# FredT232H_Board.net
KiCad netlist of a schematic drawn in EAGLE
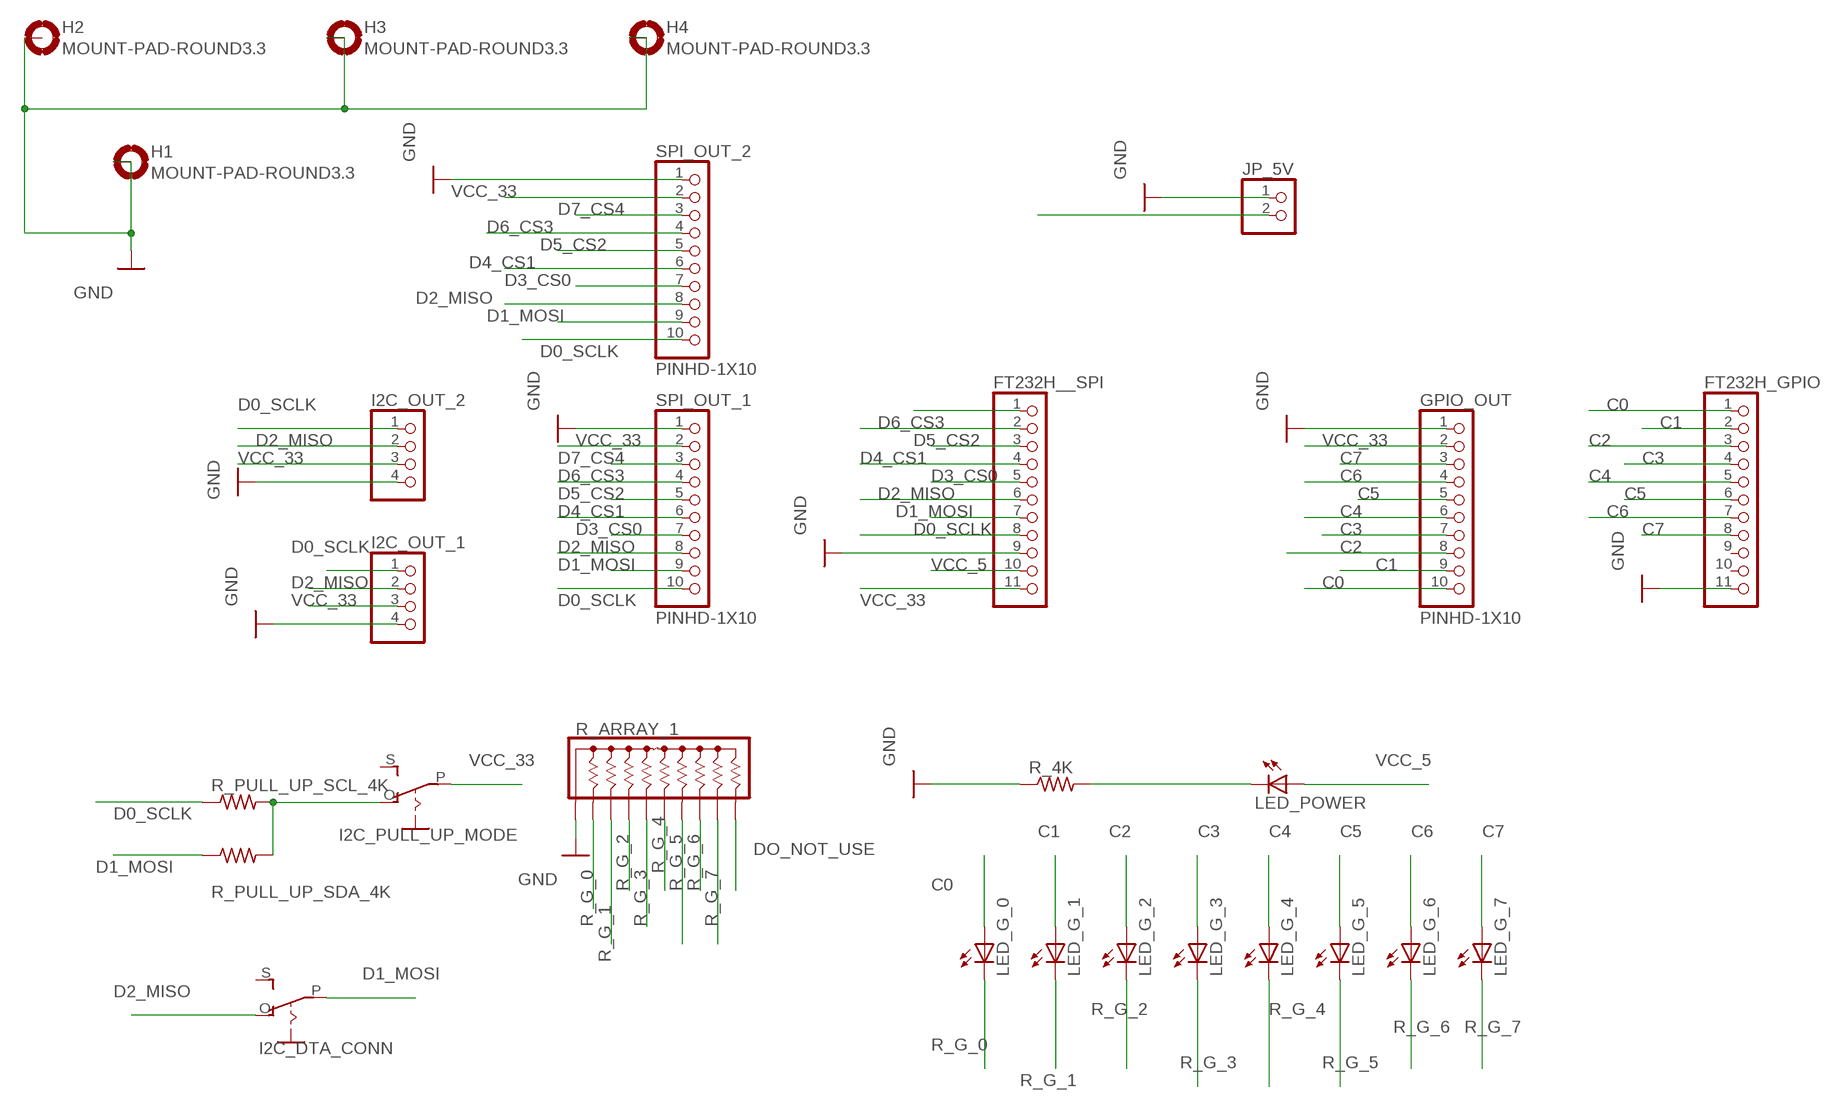
[diagram p0: schematic, sheet 1]

(export (version "E")
  (design (tool "Eeschema 10.0.6"))
  (components
    (comp (ref "FT232H_GPIO")
      (value "PINHD-1X11")
      (footprint "eagle-import:1X11")
      (libsource (lib "eagle-import") (part "PINHD-1X11"))
    )
    (comp (ref "FT232H__SPI")
      (value "PINHD-1X11")
      (footprint "eagle-import:1X11")
      (libsource (lib "eagle-import") (part "PINHD-1X11"))
    )
    (comp (ref "GPIO_OUT")
      (value "PINHD-1X10")
      (footprint "eagle-import:1X10-BIG")
      (libsource (lib "eagle-import") (part "PINHD-1X10"))
    )
    (comp (ref "H1")
      (value "MOUNT-PAD-ROUND3.3")
      (footprint "eagle-import:3,3-PAD")
      (libsource (lib "eagle-import") (part "MOUNT-PAD-ROUND3.3"))
    )
    (comp (ref "H2")
      (value "MOUNT-PAD-ROUND3.3")
      (footprint "eagle-import:3,3-PAD")
      (libsource (lib "eagle-import") (part "MOUNT-PAD-ROUND3.3"))
    )
    (comp (ref "H3")
      (value "MOUNT-PAD-ROUND3.3")
      (footprint "eagle-import:3,3-PAD")
      (libsource (lib "eagle-import") (part "MOUNT-PAD-ROUND3.3"))
    )
    (comp (ref "H4")
      (value "MOUNT-PAD-ROUND3.3")
      (footprint "eagle-import:3,3-PAD")
      (libsource (lib "eagle-import") (part "MOUNT-PAD-ROUND3.3"))
    )
    (comp (ref "I2C_DTA_CONN")
      (value "EG1218S")
      (footprint "eagle-import:EG1218")
      (libsource (lib "eagle-import") (part "EG1218S"))
    )
    (comp (ref "I2C_OUT_1")
      (value "PINHD-1X4")
      (footprint "eagle-import:1X04")
      (libsource (lib "eagle-import") (part "PINHD-1X4"))
    )
    (comp (ref "I2C_OUT_2")
      (value "PINHD-1X4")
      (footprint "eagle-import:1X04")
      (libsource (lib "eagle-import") (part "PINHD-1X4"))
    )
    (comp (ref "I2C_PULL_UP_MODE")
      (value "EG1218S")
      (footprint "eagle-import:EG1218")
      (libsource (lib "eagle-import") (part "EG1218S"))
    )
    (comp (ref "JP_5V")
      (value "PINHD-1X2")
      (footprint "eagle-import:1X02")
      (libsource (lib "eagle-import") (part "PINHD-1X2"))
    )
    (comp (ref "LED_G_0")
      (value "LEDSMT1206")
      (footprint "eagle-import:1206")
      (libsource (lib "eagle-import") (part "LEDSMT1206"))
    )
    (comp (ref "LED_G_1")
      (value "LEDSMT1206")
      (footprint "eagle-import:1206")
      (libsource (lib "eagle-import") (part "LEDSMT1206"))
    )
    (comp (ref "LED_G_2")
      (value "LEDSMT1206")
      (footprint "eagle-import:1206")
      (libsource (lib "eagle-import") (part "LEDSMT1206"))
    )
    (comp (ref "LED_G_3")
      (value "LEDSMT1206")
      (footprint "eagle-import:1206")
      (libsource (lib "eagle-import") (part "LEDSMT1206"))
    )
    (comp (ref "LED_G_4")
      (value "LEDSMT1206")
      (footprint "eagle-import:1206")
      (libsource (lib "eagle-import") (part "LEDSMT1206"))
    )
    (comp (ref "LED_G_5")
      (value "LEDSMT1206")
      (footprint "eagle-import:1206")
      (libsource (lib "eagle-import") (part "LEDSMT1206"))
    )
    (comp (ref "LED_G_6")
      (value "LEDSMT1206")
      (footprint "eagle-import:1206")
      (libsource (lib "eagle-import") (part "LEDSMT1206"))
    )
    (comp (ref "LED_G_7")
      (value "LEDSMT1206")
      (footprint "eagle-import:1206")
      (libsource (lib "eagle-import") (part "LEDSMT1206"))
    )
    (comp (ref "LED_POWER")
      (value "LEDSMT1206")
      (footprint "eagle-import:1206")
      (libsource (lib "eagle-import") (part "LEDSMT1206"))
    )
    (comp (ref "R_4K")
      (value "R-US_R1206")
      (footprint "eagle-import:R1206")
      (libsource (lib "eagle-import") (part "R-US_R1206"))
    )
    (comp (ref "R_ARRAY_1")
      (value "4610X")
      (footprint "eagle-import:SIP10")
      (libsource (lib "eagle-import") (part "4610X"))
    )
    (comp (ref "R_PULL_UP_SCL_4K")
      (value "R-US_R1206")
      (footprint "eagle-import:R1206")
      (libsource (lib "eagle-import") (part "R-US_R1206"))
    )
    (comp (ref "R_PULL_UP_SDA_4K")
      (value "R-US_R1206")
      (footprint "eagle-import:R1206")
      (libsource (lib "eagle-import") (part "R-US_R1206"))
    )
    (comp (ref "SPI_OUT_1")
      (value "PINHD-1X10")
      (footprint "eagle-import:1X10-BIG")
      (libsource (lib "eagle-import") (part "PINHD-1X10"))
    )
    (comp (ref "SPI_OUT_2")
      (value "PINHD-1X10")
      (footprint "eagle-import:1X10-BIG")
      (libsource (lib "eagle-import") (part "PINHD-1X10"))
    )
  )
  (nets
    (net (code "1") (name "/C0") (class "Default")
      (node (ref "FT232H_GPIO") (pin "1") (pinfunction "1_1") (pintype "passive"))
      (node (ref "GPIO_OUT") (pin "10") (pinfunction "10_10") (pintype "passive"))
      (node (ref "LED_G_0") (pin "A") (pinfunction "A_A") (pintype "passive"))
    )
    (net (code "2") (name "/C1") (class "Default")
      (node (ref "FT232H_GPIO") (pin "2") (pinfunction "2_2") (pintype "passive"))
      (node (ref "GPIO_OUT") (pin "9") (pinfunction "9_9") (pintype "passive"))
      (node (ref "LED_G_1") (pin "A") (pinfunction "A_A") (pintype "passive"))
    )
    (net (code "3") (name "/C2") (class "Default")
      (node (ref "FT232H_GPIO") (pin "3") (pinfunction "3_3") (pintype "passive"))
      (node (ref "GPIO_OUT") (pin "8") (pinfunction "8_8") (pintype "passive"))
      (node (ref "LED_G_2") (pin "A") (pinfunction "A_A") (pintype "passive"))
    )
    (net (code "4") (name "/C3") (class "Default")
      (node (ref "FT232H_GPIO") (pin "4") (pinfunction "4_4") (pintype "passive"))
      (node (ref "GPIO_OUT") (pin "7") (pinfunction "7_7") (pintype "passive"))
      (node (ref "LED_G_3") (pin "A") (pinfunction "A_A") (pintype "passive"))
    )
    (net (code "5") (name "/C4") (class "Default")
      (node (ref "FT232H_GPIO") (pin "5") (pinfunction "5_5") (pintype "passive"))
      (node (ref "GPIO_OUT") (pin "6") (pinfunction "6_6") (pintype "passive"))
      (node (ref "LED_G_4") (pin "A") (pinfunction "A_A") (pintype "passive"))
    )
    (net (code "6") (name "/C5") (class "Default")
      (node (ref "FT232H_GPIO") (pin "6") (pinfunction "6_6") (pintype "passive"))
      (node (ref "GPIO_OUT") (pin "5") (pinfunction "5_5") (pintype "passive"))
      (node (ref "LED_G_5") (pin "A") (pinfunction "A_A") (pintype "passive"))
    )
    (net (code "7") (name "/C6") (class "Default")
      (node (ref "FT232H_GPIO") (pin "7") (pinfunction "7_7") (pintype "passive"))
      (node (ref "GPIO_OUT") (pin "4") (pinfunction "4_4") (pintype "passive"))
      (node (ref "LED_G_6") (pin "A") (pinfunction "A_A") (pintype "passive"))
    )
    (net (code "8") (name "/C7") (class "Default")
      (node (ref "FT232H_GPIO") (pin "8") (pinfunction "8_8") (pintype "passive"))
      (node (ref "GPIO_OUT") (pin "3") (pinfunction "3_3") (pintype "passive"))
      (node (ref "LED_G_7") (pin "A") (pinfunction "A_A") (pintype "passive"))
    )
    (net (code "9") (name "/D0_SCLK") (class "Default")
      (node (ref "FT232H__SPI") (pin "8") (pinfunction "8_8") (pintype "passive"))
      (node (ref "I2C_OUT_1") (pin "1") (pinfunction "1_1") (pintype "passive"))
      (node (ref "I2C_OUT_2") (pin "1") (pinfunction "1_1") (pintype "passive"))
      (node (ref "R_PULL_UP_SCL_4K") (pin "1") (pinfunction "1_1") (pintype "passive"))
      (node (ref "SPI_OUT_1") (pin "10") (pinfunction "10_10") (pintype "passive"))
      (node (ref "SPI_OUT_2") (pin "10") (pinfunction "10_10") (pintype "passive"))
    )
    (net (code "10") (name "/D1_MOSI") (class "Default")
      (node (ref "FT232H__SPI") (pin "7") (pinfunction "7_7") (pintype "passive"))
      (node (ref "I2C_DTA_CONN") (pin "P") (pinfunction "P_P") (pintype "passive"))
      (node (ref "R_PULL_UP_SDA_4K") (pin "1") (pinfunction "1_1") (pintype "passive"))
      (node (ref "SPI_OUT_1") (pin "9") (pinfunction "9_9") (pintype "passive"))
      (node (ref "SPI_OUT_2") (pin "9") (pinfunction "9_9") (pintype "passive"))
    )
    (net (code "11") (name "/D2_MISO") (class "Default")
      (node (ref "FT232H__SPI") (pin "6") (pinfunction "6_6") (pintype "passive"))
      (node (ref "I2C_DTA_CONN") (pin "O") (pinfunction "O_O") (pintype "passive"))
      (node (ref "I2C_OUT_1") (pin "2") (pinfunction "2_2") (pintype "passive"))
      (node (ref "I2C_OUT_2") (pin "2") (pinfunction "2_2") (pintype "passive"))
      (node (ref "SPI_OUT_1") (pin "8") (pinfunction "8_8") (pintype "passive"))
      (node (ref "SPI_OUT_2") (pin "8") (pinfunction "8_8") (pintype "passive"))
    )
    (net (code "12") (name "/D3_CS0") (class "Default")
      (node (ref "FT232H__SPI") (pin "5") (pinfunction "5_5") (pintype "passive"))
      (node (ref "SPI_OUT_1") (pin "7") (pinfunction "7_7") (pintype "passive"))
      (node (ref "SPI_OUT_2") (pin "7") (pinfunction "7_7") (pintype "passive"))
    )
    (net (code "13") (name "/D4_CS1") (class "Default")
      (node (ref "FT232H__SPI") (pin "4") (pinfunction "4_4") (pintype "passive"))
      (node (ref "SPI_OUT_1") (pin "6") (pinfunction "6_6") (pintype "passive"))
      (node (ref "SPI_OUT_2") (pin "6") (pinfunction "6_6") (pintype "passive"))
    )
    (net (code "14") (name "/D5_CS2") (class "Default")
      (node (ref "FT232H__SPI") (pin "3") (pinfunction "3_3") (pintype "passive"))
      (node (ref "SPI_OUT_1") (pin "5") (pinfunction "5_5") (pintype "passive"))
      (node (ref "SPI_OUT_2") (pin "5") (pinfunction "5_5") (pintype "passive"))
    )
    (net (code "15") (name "/D6_CS3") (class "Default")
      (node (ref "FT232H__SPI") (pin "2") (pinfunction "2_2") (pintype "passive"))
      (node (ref "SPI_OUT_1") (pin "4") (pinfunction "4_4") (pintype "passive"))
      (node (ref "SPI_OUT_2") (pin "4") (pinfunction "4_4") (pintype "passive"))
    )
    (net (code "16") (name "/D7_CS4") (class "Default")
      (node (ref "FT232H__SPI") (pin "1") (pinfunction "1_1") (pintype "passive"))
      (node (ref "SPI_OUT_1") (pin "3") (pinfunction "3_3") (pintype "passive"))
      (node (ref "SPI_OUT_2") (pin "3") (pinfunction "3_3") (pintype "passive"))
    )
    (net (code "17") (name "/DO_NOT_USE") (class "Default")
      (node (ref "R_ARRAY_1") (pin "10") (pinfunction "10_10") (pintype "passive"))
    )
    (net (code "18") (name "/R_G_0") (class "Default")
      (node (ref "LED_G_0") (pin "C") (pinfunction "C_C") (pintype "passive"))
      (node (ref "R_ARRAY_1") (pin "2") (pinfunction "2_2") (pintype "passive"))
    )
    (net (code "19") (name "/R_G_1") (class "Default")
      (node (ref "LED_G_1") (pin "C") (pinfunction "C_C") (pintype "passive"))
      (node (ref "R_ARRAY_1") (pin "3") (pinfunction "3_3") (pintype "passive"))
    )
    (net (code "20") (name "/R_G_2") (class "Default")
      (node (ref "LED_G_2") (pin "C") (pinfunction "C_C") (pintype "passive"))
      (node (ref "R_ARRAY_1") (pin "4") (pinfunction "4_4") (pintype "passive"))
    )
    (net (code "21") (name "/R_G_3") (class "Default")
      (node (ref "LED_G_3") (pin "C") (pinfunction "C_C") (pintype "passive"))
      (node (ref "R_ARRAY_1") (pin "5") (pinfunction "5_5") (pintype "passive"))
    )
    (net (code "22") (name "/R_G_4") (class "Default")
      (node (ref "LED_G_4") (pin "C") (pinfunction "C_C") (pintype "passive"))
      (node (ref "R_ARRAY_1") (pin "6") (pinfunction "6_6") (pintype "passive"))
    )
    (net (code "23") (name "/R_G_5") (class "Default")
      (node (ref "LED_G_5") (pin "C") (pinfunction "C_C") (pintype "passive"))
      (node (ref "R_ARRAY_1") (pin "7") (pinfunction "7_7") (pintype "passive"))
    )
    (net (code "24") (name "/R_G_6") (class "Default")
      (node (ref "LED_G_6") (pin "C") (pinfunction "C_C") (pintype "passive"))
      (node (ref "R_ARRAY_1") (pin "8") (pinfunction "8_8") (pintype "passive"))
    )
    (net (code "25") (name "/R_G_7") (class "Default")
      (node (ref "LED_G_7") (pin "C") (pinfunction "C_C") (pintype "passive"))
      (node (ref "R_ARRAY_1") (pin "9") (pinfunction "9_9") (pintype "passive"))
    )
    (net (code "26") (name "/VCC_5") (class "Default")
      (node (ref "FT232H__SPI") (pin "10") (pinfunction "10_10") (pintype "passive"))
      (node (ref "JP_5V") (pin "2") (pinfunction "2_2") (pintype "passive"))
      (node (ref "LED_POWER") (pin "A") (pinfunction "A_A") (pintype "passive"))
    )
    (net (code "27") (name "/VCC_33") (class "Default")
      (node (ref "FT232H__SPI") (pin "11") (pinfunction "11_11") (pintype "passive"))
      (node (ref "GPIO_OUT") (pin "2") (pinfunction "2_2") (pintype "passive"))
      (node (ref "I2C_OUT_1") (pin "3") (pinfunction "3_3") (pintype "passive"))
      (node (ref "I2C_OUT_2") (pin "3") (pinfunction "3_3") (pintype "passive"))
      (node (ref "I2C_PULL_UP_MODE") (pin "P") (pinfunction "P_P") (pintype "passive"))
      (node (ref "SPI_OUT_1") (pin "2") (pinfunction "2_2") (pintype "passive"))
      (node (ref "SPI_OUT_2") (pin "2") (pinfunction "2_2") (pintype "passive"))
    )
    (net (code "28") (name "GND") (class "Default")
      (node (ref "FT232H_GPIO") (pin "11") (pinfunction "11_11") (pintype "passive"))
      (node (ref "FT232H__SPI") (pin "9") (pinfunction "9_9") (pintype "passive"))
      (node (ref "GPIO_OUT") (pin "1") (pinfunction "1_1") (pintype "passive"))
      (node (ref "H1") (pin "B3,3") (pinfunction "MOUNT_B3,3") (pintype "passive"))
      (node (ref "H2") (pin "B3,3") (pinfunction "MOUNT_B3,3") (pintype "passive"))
      (node (ref "H3") (pin "B3,3") (pinfunction "MOUNT_B3,3") (pintype "passive"))
      (node (ref "H4") (pin "B3,3") (pinfunction "MOUNT_B3,3") (pintype "passive"))
      (node (ref "I2C_OUT_1") (pin "4") (pinfunction "4_4") (pintype "passive"))
      (node (ref "I2C_OUT_2") (pin "4") (pinfunction "4_4") (pintype "passive"))
      (node (ref "JP_5V") (pin "1") (pinfunction "1_1") (pintype "passive"))
      (node (ref "R_4K") (pin "1") (pinfunction "1_1") (pintype "passive"))
      (node (ref "R_ARRAY_1") (pin "1") (pinfunction "1_1") (pintype "passive"))
      (node (ref "SPI_OUT_1") (pin "1") (pinfunction "1_1") (pintype "passive"))
      (node (ref "SPI_OUT_2") (pin "1") (pinfunction "1_1") (pintype "passive"))
    )
    (net (code "29") (name "Net-(I2C_PULL_UP_MODE-PadO)") (class "Default")
      (node (ref "I2C_PULL_UP_MODE") (pin "O") (pinfunction "O_O") (pintype "passive"))
      (node (ref "R_PULL_UP_SCL_4K") (pin "2") (pinfunction "2_2") (pintype "passive"))
      (node (ref "R_PULL_UP_SDA_4K") (pin "2") (pinfunction "2_2") (pintype "passive"))
    )
    (net (code "30") (name "Net-(LED_POWER-PadC)") (class "Default")
      (node (ref "LED_POWER") (pin "C") (pinfunction "C_C") (pintype "passive"))
      (node (ref "R_4K") (pin "2") (pinfunction "2_2") (pintype "passive"))
    )
    (net (code "31") (name "unconnected-(FT232H_GPIO-Pad9)") (class "Default")
      (node (ref "FT232H_GPIO") (pin "9") (pinfunction "9_9") (pintype "passive"))
    )
    (net (code "32") (name "unconnected-(FT232H_GPIO-Pad10)") (class "Default")
      (node (ref "FT232H_GPIO") (pin "10") (pinfunction "10_10") (pintype "passive"))
    )
    (net (code "33") (name "unconnected-(I2C_DTA_CONN-PadS)") (class "Default")
      (node (ref "I2C_DTA_CONN") (pin "S") (pinfunction "S_S") (pintype "passive"))
    )
    (net (code "34") (name "unconnected-(I2C_PULL_UP_MODE-PadS)") (class "Default")
      (node (ref "I2C_PULL_UP_MODE") (pin "S") (pinfunction "S_S") (pintype "passive"))
    )
  )
)
